# capsense1.net
KiCad netlist of a schematic drawn in EAGLE
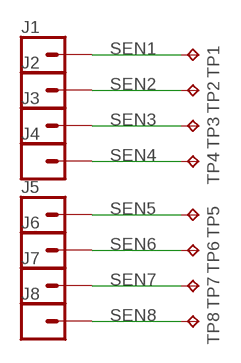
[diagram p0: schematic, sheet 1]

(export (version "E")
  (design (tool "Eeschema 10.0.6"))
  (components
    (comp (ref "J1")
      (value "CONN_01")
      (footprint "eagle-import:1X01")
      (libsource (lib "eagle-import") (part "CONN_01"))
    )
    (comp (ref "J2")
      (value "CONN_01")
      (footprint "eagle-import:1X01")
      (libsource (lib "eagle-import") (part "CONN_01"))
    )
    (comp (ref "J3")
      (value "CONN_01")
      (footprint "eagle-import:1X01")
      (libsource (lib "eagle-import") (part "CONN_01"))
    )
    (comp (ref "J4")
      (value "CONN_01")
      (footprint "eagle-import:1X01")
      (libsource (lib "eagle-import") (part "CONN_01"))
    )
    (comp (ref "J5")
      (value "CONN_01")
      (footprint "eagle-import:1X01")
      (libsource (lib "eagle-import") (part "CONN_01"))
    )
    (comp (ref "J6")
      (value "CONN_01")
      (footprint "eagle-import:1X01")
      (libsource (lib "eagle-import") (part "CONN_01"))
    )
    (comp (ref "J7")
      (value "CONN_01")
      (footprint "eagle-import:1X01")
      (libsource (lib "eagle-import") (part "CONN_01"))
    )
    (comp (ref "J8")
      (value "CONN_01")
      (footprint "eagle-import:1X01")
      (libsource (lib "eagle-import") (part "CONN_01"))
    )
    (comp (ref "TP1")
      (value "TPTP20R")
      (footprint "eagle-import:TP20R")
      (libsource (lib "eagle-import") (part "TPTP20R"))
    )
    (comp (ref "TP2")
      (value "TPTP20R")
      (footprint "eagle-import:TP20R")
      (libsource (lib "eagle-import") (part "TPTP20R"))
    )
    (comp (ref "TP3")
      (value "TPTP20R")
      (footprint "eagle-import:TP20R")
      (libsource (lib "eagle-import") (part "TPTP20R"))
    )
    (comp (ref "TP4")
      (value "TPTP20R")
      (footprint "eagle-import:TP20R")
      (libsource (lib "eagle-import") (part "TPTP20R"))
    )
    (comp (ref "TP5")
      (value "TPTP20R")
      (footprint "eagle-import:TP20R")
      (libsource (lib "eagle-import") (part "TPTP20R"))
    )
    (comp (ref "TP6")
      (value "TPTP20R")
      (footprint "eagle-import:TP20R")
      (libsource (lib "eagle-import") (part "TPTP20R"))
    )
    (comp (ref "TP7")
      (value "TPTP20R")
      (footprint "eagle-import:TP20R")
      (libsource (lib "eagle-import") (part "TPTP20R"))
    )
    (comp (ref "TP8")
      (value "TPTP20R")
      (footprint "eagle-import:TP20R")
      (libsource (lib "eagle-import") (part "TPTP20R"))
    )
  )
  (nets
    (net (code "1") (name "/SEN1") (class "Default")
      (node (ref "J1") (pin "1") (pinfunction "1_1") (pintype "passive"))
      (node (ref "TP1") (pin "TP") (pinfunction "TP_TP") (pintype "input"))
    )
    (net (code "2") (name "/SEN2") (class "Default")
      (node (ref "J2") (pin "1") (pinfunction "1_1") (pintype "passive"))
      (node (ref "TP2") (pin "TP") (pinfunction "TP_TP") (pintype "input"))
    )
    (net (code "3") (name "/SEN3") (class "Default")
      (node (ref "J3") (pin "1") (pinfunction "1_1") (pintype "passive"))
      (node (ref "TP3") (pin "TP") (pinfunction "TP_TP") (pintype "input"))
    )
    (net (code "4") (name "/SEN4") (class "Default")
      (node (ref "J4") (pin "1") (pinfunction "1_1") (pintype "passive"))
      (node (ref "TP4") (pin "TP") (pinfunction "TP_TP") (pintype "input"))
    )
    (net (code "5") (name "/SEN5") (class "Default")
      (node (ref "J5") (pin "1") (pinfunction "1_1") (pintype "passive"))
      (node (ref "TP5") (pin "TP") (pinfunction "TP_TP") (pintype "input"))
    )
    (net (code "6") (name "/SEN6") (class "Default")
      (node (ref "J6") (pin "1") (pinfunction "1_1") (pintype "passive"))
      (node (ref "TP6") (pin "TP") (pinfunction "TP_TP") (pintype "input"))
    )
    (net (code "7") (name "/SEN7") (class "Default")
      (node (ref "J7") (pin "1") (pinfunction "1_1") (pintype "passive"))
      (node (ref "TP7") (pin "TP") (pinfunction "TP_TP") (pintype "input"))
    )
    (net (code "8") (name "/SEN8") (class "Default")
      (node (ref "J8") (pin "1") (pinfunction "1_1") (pintype "passive"))
      (node (ref "TP8") (pin "TP") (pinfunction "TP_TP") (pintype "input"))
    )
  )
)
